# 3_-MCU.net
KiCad netlist of a schematic drawn in Altium Designer
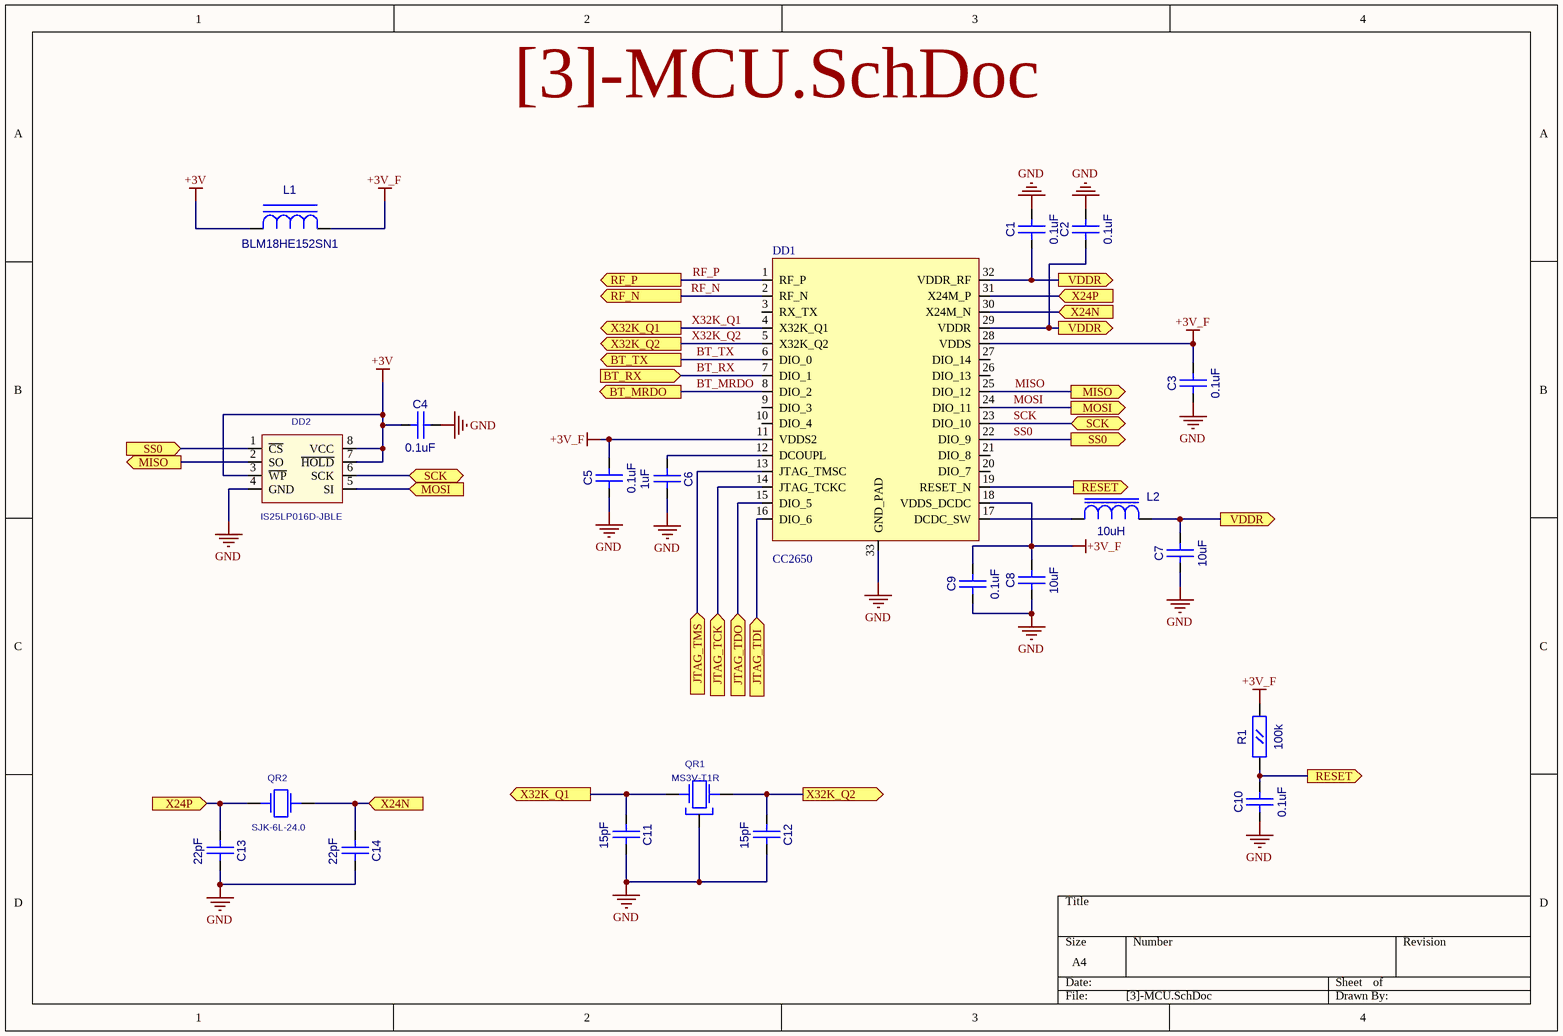
[diagram p0: [3]-MCU.SchDoc]

(export (version "E")
  (design (tool "Eeschema 10.0.6"))
  (components
    (comp (ref "C1")
      (value "0.1uF")
      (footprint "CC0603")
      (description "CC0603")
      (libsource (lib "gprs_modem_2") (part "CC0603"))
    )
    (comp (ref "C2")
      (value "0.1uF")
      (footprint "CC0603")
      (description "CC0603")
      (libsource (lib "gprs_modem_2") (part "CC0603"))
    )
    (comp (ref "C3")
      (value "0.1uF")
      (footprint "CC0603")
      (description "CC0603")
      (libsource (lib "gprs_modem_2") (part "CC0603"))
    )
    (comp (ref "C4")
      (value "0.1uF")
      (footprint "CC0603")
      (description "CC0603")
      (libsource (lib "gprs_modem_2") (part "CC0603"))
    )
    (comp (ref "C5")
      (value "0.1uF")
      (footprint "CC0603")
      (description "CC0603")
      (libsource (lib "gprs_modem_2") (part "CC0603"))
    )
    (comp (ref "C6")
      (value "1uF")
      (footprint "CC0603")
      (description "CC0603")
      (libsource (lib "gprs_modem_2") (part "CC0603"))
    )
    (comp (ref "C7")
      (value "10uF")
      (footprint "CC0805")
      (description "CC0805")
      (libsource (lib "gprs_modem_2") (part "CC0805"))
    )
    (comp (ref "C8")
      (value "10uF")
      (footprint "CC0805")
      (description "CC0805")
      (libsource (lib "gprs_modem_2") (part "CC0805"))
    )
    (comp (ref "C9")
      (value "0.1uF")
      (footprint "CC0603")
      (description "CC0603")
      (libsource (lib "gprs_modem_2") (part "CC0603"))
    )
    (comp (ref "C10")
      (value "0.1uF")
      (footprint "CC0603")
      (description "CC0603")
      (libsource (lib "gprs_modem_2") (part "CC0603"))
    )
    (comp (ref "C11")
      (value "15pF")
      (footprint "CC0603")
      (description "CC0603")
      (libsource (lib "gprs_modem_2") (part "CC0603"))
    )
    (comp (ref "C12")
      (value "15pF")
      (footprint "CC0603")
      (description "CC0603")
      (libsource (lib "gprs_modem_2") (part "CC0603"))
    )
    (comp (ref "C13")
      (value "22pF")
      (footprint "CC0603")
      (description "CC0603")
      (libsource (lib "gprs_modem_2") (part "CC0603"))
    )
    (comp (ref "C14")
      (value "22pF")
      (footprint "CC0603")
      (description "CC0603")
      (libsource (lib "gprs_modem_2") (part "CC0603"))
    )
    (comp (ref "DD1")
      (value "CC2650")
      (footprint "QFN32_TI")
      (description "CC2650RHBT")
      (libsource (lib "gprs_modem_2") (part "CC2650RHB"))
    )
    (comp (ref "DD2")
      (value "IS25LP016D-JBLE")
      (footprint "EIAJ_SO8")
      (description "S25FL016A0LMFI01")
      (libsource (lib "fizik_lib") (part "S25FL016A0LMFI01"))
    )
    (comp (ref "L1")
      (value "BLM18HE152SN1")
      (footprint "L0603")
      (description "L0603")
      (libsource (lib "gprs_modem_2") (part "L0603"))
    )
    (comp (ref "L2")
      (value "10uH")
      (footprint "RC0805")
      (description "L0805")
      (libsource (lib "gprs_modem_2") (part "L0805"))
    )
    (comp (ref "QR1")
      (value "MS3V-T1R")
      (footprint "MS3V-T1R")
      (description "CRYSTAL_32768 Hz")
      (libsource (lib "gprs_modem_2") (part "MS3V-T1R"))
    )
    (comp (ref "QR2")
      (value "SJK-6L-24.0")
      (footprint "AC5032_2")
      (description "AC5032/2")
      (libsource (lib "gprs_modem_2") (part "AC5032_2"))
    )
    (comp (ref "R1")
      (value "100k")
      (footprint "RC0603")
      (description "RC0603")
      (libsource (lib "gprs_modem_2") (part "RC0603"))
    )
  )
  (nets
    (net (code "1") (name "+3V") (class "Default")
      (node (ref "C4") (pin "1") (pinfunction "A_1") (pintype "passive"))
      (node (ref "DD2") (pin "3") (pinfunction "~{WP}_3") (pintype "passive"))
      (node (ref "DD2") (pin "7") (pinfunction "~{HOLD}_7") (pintype "passive"))
      (node (ref "DD2") (pin "8") (pinfunction "VCC_8") (pintype "passive"))
      (node (ref "L1") (pin "1") (pinfunction "A_1") (pintype "passive"))
    )
    (net (code "2") (name "+3V_F") (class "Default")
      (node (ref "C3") (pin "2") (pinfunction "B_2") (pintype "passive"))
      (node (ref "C5") (pin "2") (pinfunction "B_2") (pintype "passive"))
      (node (ref "C8") (pin "2") (pinfunction "B_2") (pintype "passive"))
      (node (ref "C9") (pin "2") (pinfunction "B_2") (pintype "passive"))
      (node (ref "DD1") (pin "11") (pinfunction "VDDS2_11") (pintype "passive"))
      (node (ref "DD1") (pin "18") (pinfunction "VDDS_DCDC_18") (pintype "passive"))
      (node (ref "DD1") (pin "28") (pinfunction "VDDS_28") (pintype "passive"))
      (node (ref "L1") (pin "2") (pinfunction "C_2") (pintype "passive"))
      (node (ref "R1") (pin "2") (pinfunction "B_2") (pintype "passive"))
    )
    (net (code "3") (name "/BT_MRDO") (class "Default")
      (node (ref "DD1") (pin "8") (pinfunction "DIO_2_8") (pintype "passive"))
    )
    (net (code "4") (name "/BT_RX") (class "Default")
      (node (ref "DD1") (pin "7") (pinfunction "DIO_1_7") (pintype "passive"))
    )
    (net (code "5") (name "/BT_TX") (class "Default")
      (node (ref "DD1") (pin "6") (pinfunction "DIO_0_6") (pintype "passive"))
    )
    (net (code "6") (name "/JTAG_TCK") (class "Default")
      (node (ref "DD1") (pin "14") (pinfunction "JTAG_TCKC_14") (pintype "passive"))
    )
    (net (code "7") (name "/JTAG_TDI") (class "Default")
      (node (ref "DD1") (pin "16") (pinfunction "DIO_6_16") (pintype "passive"))
    )
    (net (code "8") (name "/JTAG_TDO") (class "Default")
      (node (ref "DD1") (pin "15") (pinfunction "DIO_5_15") (pintype "passive"))
    )
    (net (code "9") (name "/JTAG_TMS") (class "Default")
      (node (ref "DD1") (pin "13") (pinfunction "JTAG_TMSC_13") (pintype "passive"))
    )
    (net (code "10") (name "/MISO") (class "Default")
      (node (ref "DD1") (pin "25") (pinfunction "DIO_12_25") (pintype "passive"))
      (node (ref "DD2") (pin "2") (pinfunction "SO_2") (pintype "passive"))
    )
    (net (code "11") (name "/MOSI") (class "Default")
      (node (ref "DD1") (pin "24") (pinfunction "DIO_11_24") (pintype "passive"))
      (node (ref "DD2") (pin "5") (pinfunction "SI_5") (pintype "passive"))
    )
    (net (code "12") (name "/RESET") (class "Default")
      (node (ref "C10") (pin "2") (pinfunction "B_2") (pintype "passive"))
      (node (ref "DD1") (pin "19") (pinfunction "RESET_N_19") (pintype "passive"))
      (node (ref "R1") (pin "1") (pinfunction "A_1") (pintype "passive"))
    )
    (net (code "13") (name "/RF_N") (class "Default")
      (node (ref "DD1") (pin "2") (pinfunction "RF_N_2") (pintype "passive"))
    )
    (net (code "14") (name "/RF_P") (class "Default")
      (node (ref "DD1") (pin "1") (pinfunction "RF_P_1") (pintype "passive"))
    )
    (net (code "15") (name "/SCK") (class "Default")
      (node (ref "DD1") (pin "23") (pinfunction "DIO_10_23") (pintype "passive"))
      (node (ref "DD2") (pin "6") (pinfunction "SCK_6") (pintype "passive"))
    )
    (net (code "16") (name "/SS0") (class "Default")
      (node (ref "DD1") (pin "22") (pinfunction "DIO_9_22") (pintype "passive"))
      (node (ref "DD2") (pin "1") (pinfunction "~{CS}_1") (pintype "passive"))
    )
    (net (code "17") (name "/VDDR") (class "Default")
      (node (ref "C1") (pin "1") (pinfunction "A_1") (pintype "passive"))
      (node (ref "C2") (pin "1") (pinfunction "A_1") (pintype "passive"))
      (node (ref "C7") (pin "2") (pinfunction "B_2") (pintype "passive"))
      (node (ref "DD1") (pin "29") (pinfunction "VDDR_29") (pintype "passive"))
      (node (ref "DD1") (pin "32") (pinfunction "VDDR_RF_32") (pintype "passive"))
      (node (ref "L2") (pin "2") (pinfunction "B_2") (pintype "passive"))
    )
    (net (code "18") (name "/X24N") (class "Default")
      (node (ref "C14") (pin "1") (pinfunction "A_1") (pintype "passive"))
      (node (ref "DD1") (pin "30") (pinfunction "X24M_N_30") (pintype "passive"))
      (node (ref "QR2") (pin "2") (pintype "passive"))
    )
    (net (code "19") (name "/X24P") (class "Default")
      (node (ref "C13") (pin "1") (pinfunction "A_1") (pintype "passive"))
      (node (ref "DD1") (pin "31") (pinfunction "X24M_P_31") (pintype "passive"))
      (node (ref "QR2") (pin "1") (pintype "passive"))
    )
    (net (code "20") (name "/X32K_Q1") (class "Default")
      (node (ref "C11") (pin "1") (pinfunction "A_1") (pintype "passive"))
      (node (ref "DD1") (pin "4") (pinfunction "X32K_Q1_4") (pintype "passive"))
      (node (ref "QR1") (pin "2") (pinfunction "X2_2") (pintype "passive"))
    )
    (net (code "21") (name "/X32K_Q2") (class "Default")
      (node (ref "C12") (pin "1") (pinfunction "A_1") (pintype "passive"))
      (node (ref "DD1") (pin "5") (pinfunction "X32K_Q2_5") (pintype "passive"))
      (node (ref "QR1") (pin "1") (pinfunction "X1_1") (pintype "passive"))
    )
    (net (code "22") (name "GND") (class "Default")
      (node (ref "C1") (pin "2") (pinfunction "B_2") (pintype "passive"))
      (node (ref "C10") (pin "1") (pinfunction "A_1") (pintype "passive"))
      (node (ref "C11") (pin "2") (pinfunction "B_2") (pintype "passive"))
      (node (ref "C12") (pin "2") (pinfunction "B_2") (pintype "passive"))
      (node (ref "C13") (pin "2") (pinfunction "B_2") (pintype "passive"))
      (node (ref "C14") (pin "2") (pinfunction "B_2") (pintype "passive"))
      (node (ref "C2") (pin "2") (pinfunction "B_2") (pintype "passive"))
      (node (ref "C3") (pin "1") (pinfunction "A_1") (pintype "passive"))
      (node (ref "C4") (pin "2") (pinfunction "B_2") (pintype "passive"))
      (node (ref "C5") (pin "1") (pinfunction "A_1") (pintype "passive"))
      (node (ref "C6") (pin "2") (pinfunction "B_2") (pintype "passive"))
      (node (ref "C7") (pin "1") (pinfunction "A_1") (pintype "passive"))
      (node (ref "C8") (pin "1") (pinfunction "A_1") (pintype "passive"))
      (node (ref "C9") (pin "1") (pinfunction "A_1") (pintype "passive"))
      (node (ref "DD1") (pin "33") (pinfunction "GND_PAD_33") (pintype "passive"))
      (node (ref "DD2") (pin "4") (pinfunction "GND_4") (pintype "passive"))
      (node (ref "QR1") (pin "3") (pinfunction "3_3") (pintype "passive"))
    )
    (net (code "23") (name "Net-(C6-A)") (class "Default")
      (node (ref "C6") (pin "1") (pinfunction "A_1") (pintype "passive"))
      (node (ref "DD1") (pin "12") (pinfunction "DCOUPL_12") (pintype "passive"))
    )
    (net (code "24") (name "Net-(DD1-DCDC_SW)") (class "Default")
      (node (ref "DD1") (pin "17") (pinfunction "DCDC_SW_17") (pintype "passive"))
      (node (ref "L2") (pin "1") (pinfunction "A_1") (pintype "passive"))
    )
    (net (code "25") (name "unconnected-(DD1-DIO_3-Pad9)") (class "Default")
      (node (ref "DD1") (pin "9") (pinfunction "DIO_3_9") (pintype "passive"))
    )
    (net (code "26") (name "unconnected-(DD1-DIO_4-Pad10)") (class "Default")
      (node (ref "DD1") (pin "10") (pinfunction "DIO_4_10") (pintype "passive"))
    )
    (net (code "27") (name "unconnected-(DD1-DIO_7-Pad20)") (class "Default")
      (node (ref "DD1") (pin "20") (pinfunction "DIO_7_20") (pintype "passive"))
    )
    (net (code "28") (name "unconnected-(DD1-DIO_8-Pad21)") (class "Default")
      (node (ref "DD1") (pin "21") (pinfunction "DIO_8_21") (pintype "passive"))
    )
    (net (code "29") (name "unconnected-(DD1-DIO_13-Pad26)") (class "Default")
      (node (ref "DD1") (pin "26") (pinfunction "DIO_13_26") (pintype "passive"))
    )
    (net (code "30") (name "unconnected-(DD1-DIO_14-Pad27)") (class "Default")
      (node (ref "DD1") (pin "27") (pinfunction "DIO_14_27") (pintype "passive"))
    )
    (net (code "31") (name "unconnected-(DD1-RX_TX-Pad3)") (class "Default")
      (node (ref "DD1") (pin "3") (pinfunction "RX_TX_3") (pintype "passive"))
    )
  )
)
